# k22a.net
KiCad netlist of a schematic drawn in EAGLE
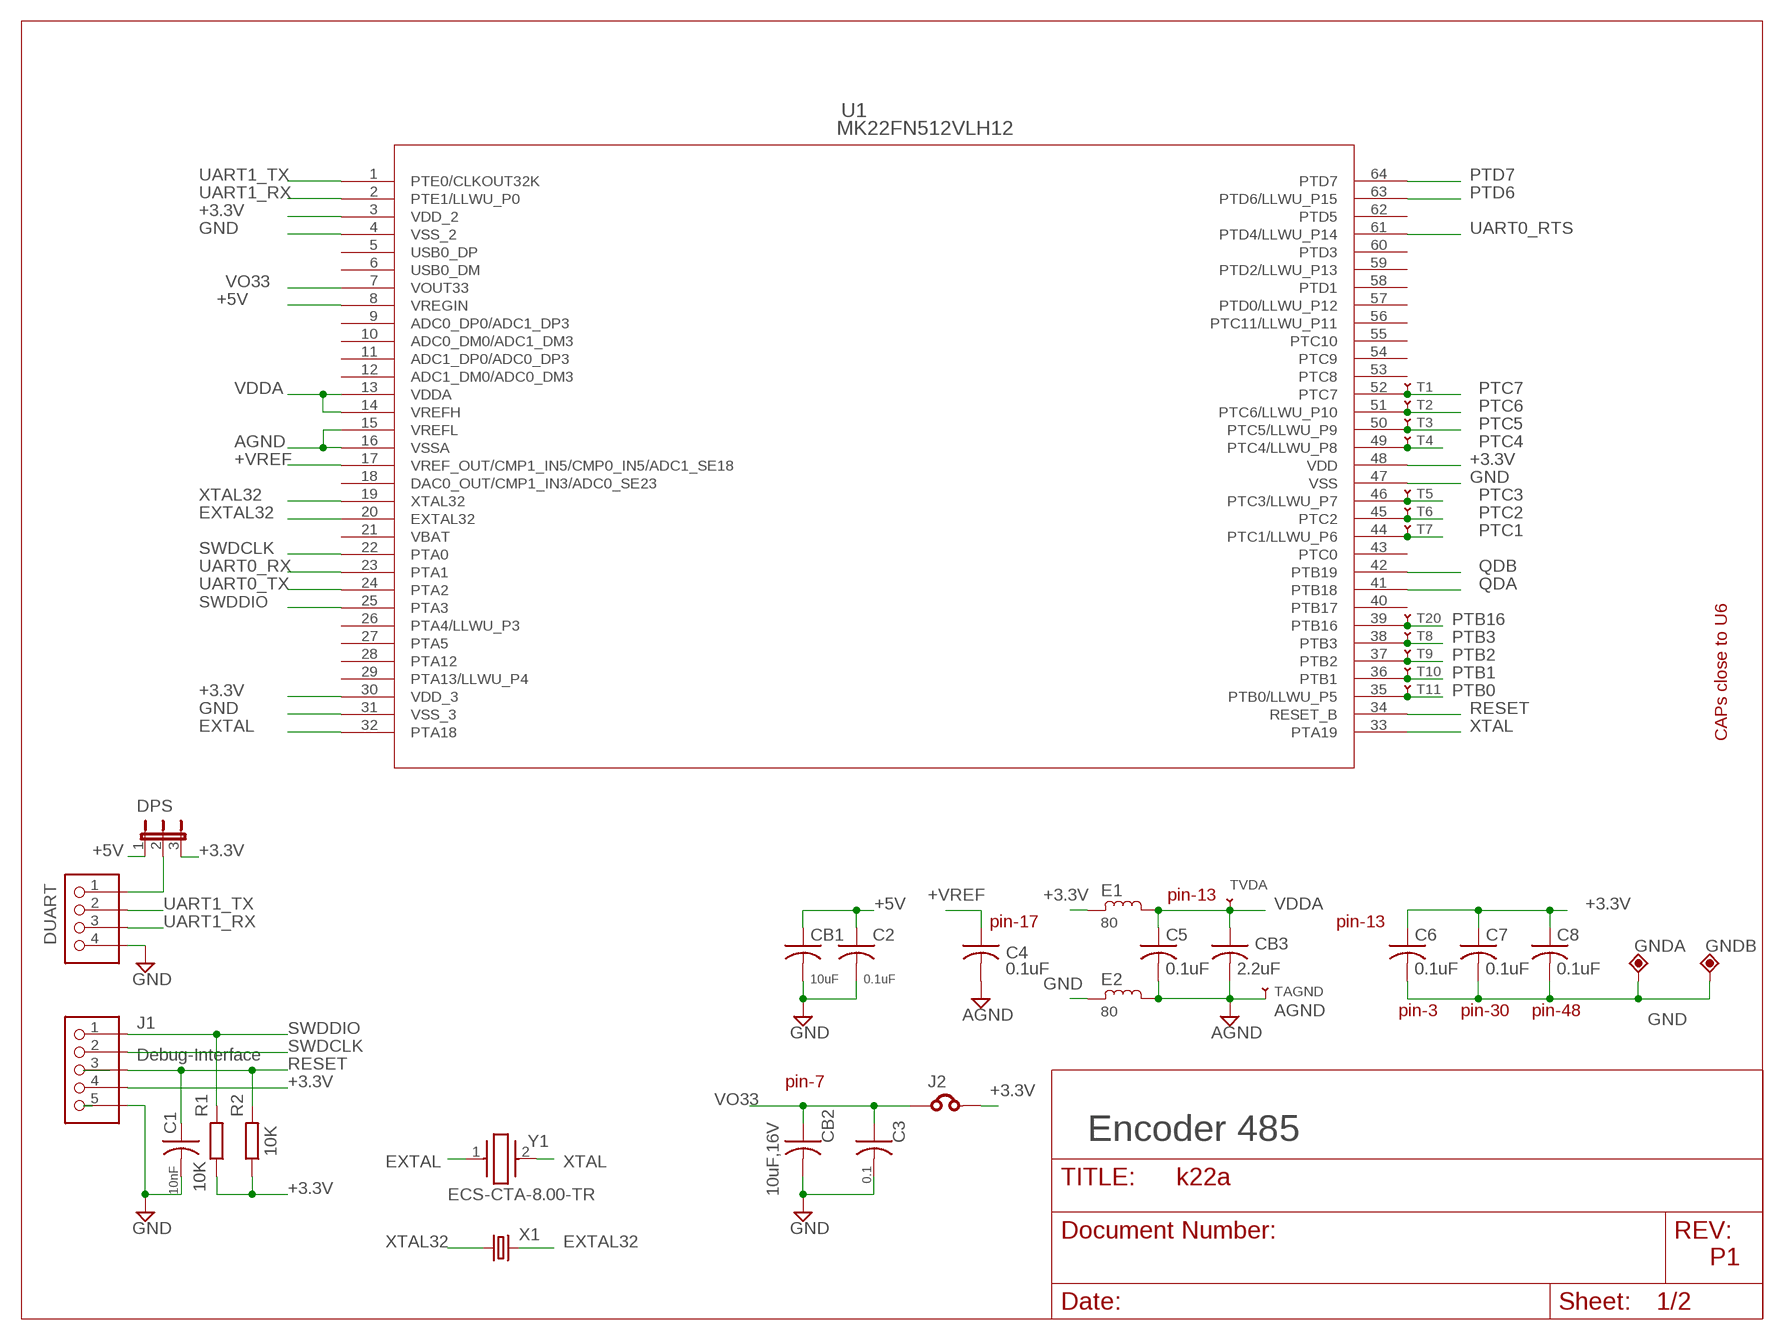
[diagram p0: schematic, sheet 1]
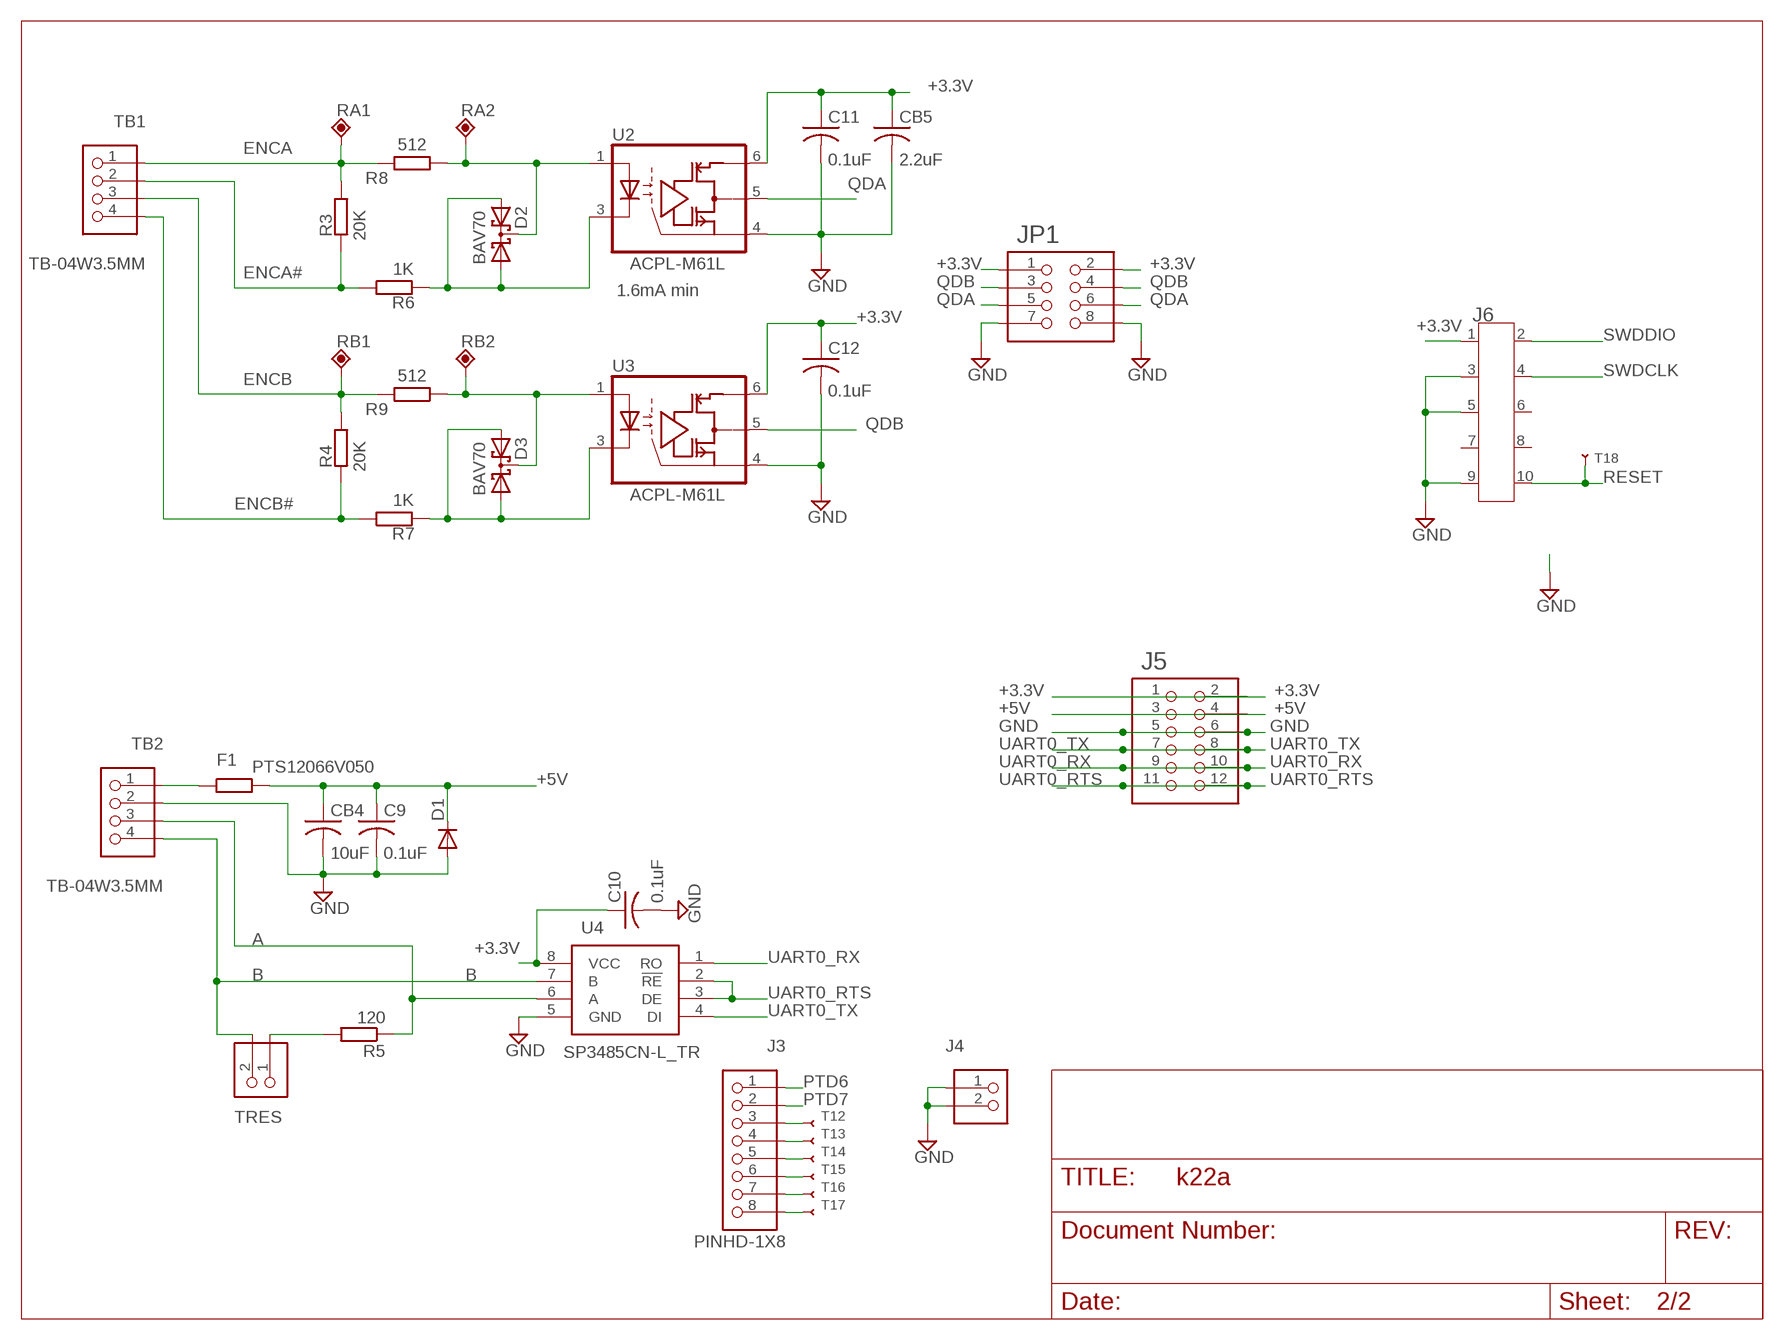
[diagram p1: schematic, sheet 2]

(export (version "E")
  (design (tool "Eeschema 10.0.6"))
  (components
    (comp (ref "C1")
      (value "10nF")
      (footprint "eagle-import:C1206")
      (libsource (lib "eagle-import") (part "C-USC1206"))
    )
    (comp (ref "C2")
      (value "0.1uF")
      (footprint "eagle-import:C1206")
      (libsource (lib "eagle-import") (part "C-USC1206"))
    )
    (comp (ref "C3")
      (value "0.1")
      (footprint "eagle-import:C1206")
      (libsource (lib "eagle-import") (part "C-USC1206"))
    )
    (comp (ref "C4")
      (value "0.1uF")
      (footprint "eagle-import:C1206")
      (libsource (lib "eagle-import") (part "C-USC1206"))
    )
    (comp (ref "C5")
      (value "0.1uF")
      (footprint "eagle-import:C1206")
      (libsource (lib "eagle-import") (part "C-USC1206"))
    )
    (comp (ref "C6")
      (value "0.1uF")
      (footprint "eagle-import:C1206")
      (libsource (lib "eagle-import") (part "C-USC1206"))
    )
    (comp (ref "C7")
      (value "0.1uF")
      (footprint "eagle-import:C1206")
      (libsource (lib "eagle-import") (part "C-USC1206"))
    )
    (comp (ref "C8")
      (value "0.1uF")
      (footprint "eagle-import:C1206")
      (libsource (lib "eagle-import") (part "C-USC1206"))
    )
    (comp (ref "CB1")
      (value "10uF")
      (footprint "eagle-import:C1206")
      (libsource (lib "eagle-import") (part "C-USC1206"))
    )
    (comp (ref "CB2")
      (value "10uF,16V")
      (footprint "eagle-import:C1206")
      (libsource (lib "eagle-import") (part "C-USC1206"))
    )
    (comp (ref "CB3")
      (value "2.2uF")
      (footprint "eagle-import:C1206")
      (libsource (lib "eagle-import") (part "C-USC1206"))
    )
    (comp (ref "DPS")
      (value "JP2E-0805")
      (footprint "eagle-import:R0805_2")
      (libsource (lib "eagle-import") (part "JP2E-0805"))
    )
    (comp (ref "DUART")
      (value "PINHD-1X4")
      (footprint "eagle-import:1X4")
      (libsource (lib "eagle-import") (part "PINHD-1X4"))
    )
    (comp (ref "E1")
      (value "80")
      (footprint "eagle-import:M1206")
      (libsource (lib "eagle-import") (part "ELDRC25SMD"))
    )
    (comp (ref "E2")
      (value "80")
      (footprint "eagle-import:M1206")
      (libsource (lib "eagle-import") (part "ELDRC25SMD"))
    )
    (comp (ref "GNDA")
      (value "TPP-PAD-032")
      (footprint "eagle-import:PAD-032")
      (libsource (lib "eagle-import") (part "TPP-PAD-032"))
    )
    (comp (ref "GNDB")
      (value "TPP-PAD-032")
      (footprint "eagle-import:PAD-032")
      (libsource (lib "eagle-import") (part "TPP-PAD-032"))
    )
    (comp (ref "J1")
      (value "PINHD-1X52MM")
      (footprint "eagle-import:1X5_2MM")
      (libsource (lib "eagle-import") (part "PINHD-1X52MM"))
    )
    (comp (ref "J2")
      (value "J0805")
      (footprint "eagle-import:R0805")
      (libsource (lib "eagle-import") (part "J0805"))
    )
    (comp (ref "R1")
      (value "10K")
      (footprint "eagle-import:M1206")
      (libsource (lib "eagle-import") (part "R-EU_M1206"))
    )
    (comp (ref "R2")
      (value "10K")
      (footprint "eagle-import:M1206")
      (libsource (lib "eagle-import") (part "R-EU_M1206"))
    )
    (comp (ref "T1")
      (value "ATP-40")
      (footprint "eagle-import:ATP-40")
      (libsource (lib "eagle-import") (part "ATP-40"))
    )
    (comp (ref "T2")
      (value "ATP-40")
      (footprint "eagle-import:ATP-40")
      (libsource (lib "eagle-import") (part "ATP-40"))
    )
    (comp (ref "T3")
      (value "ATP-40")
      (footprint "eagle-import:ATP-40")
      (libsource (lib "eagle-import") (part "ATP-40"))
    )
    (comp (ref "T4")
      (value "ATP-40")
      (footprint "eagle-import:ATP-40")
      (libsource (lib "eagle-import") (part "ATP-40"))
    )
    (comp (ref "T5")
      (value "ATP-40")
      (footprint "eagle-import:ATP-40")
      (libsource (lib "eagle-import") (part "ATP-40"))
    )
    (comp (ref "T6")
      (value "ATP-40")
      (footprint "eagle-import:ATP-40")
      (libsource (lib "eagle-import") (part "ATP-40"))
    )
    (comp (ref "T7")
      (value "ATP-40")
      (footprint "eagle-import:ATP-40")
      (libsource (lib "eagle-import") (part "ATP-40"))
    )
    (comp (ref "T8")
      (value "ATP-40")
      (footprint "eagle-import:ATP-40")
      (libsource (lib "eagle-import") (part "ATP-40"))
    )
    (comp (ref "T9")
      (value "ATP-40")
      (footprint "eagle-import:ATP-40")
      (libsource (lib "eagle-import") (part "ATP-40"))
    )
    (comp (ref "T10")
      (value "ATP-40")
      (footprint "eagle-import:ATP-40")
      (libsource (lib "eagle-import") (part "ATP-40"))
    )
    (comp (ref "T11")
      (value "ATP-40")
      (footprint "eagle-import:ATP-40")
      (libsource (lib "eagle-import") (part "ATP-40"))
    )
    (comp (ref "T20")
      (value "ATP-40")
      (footprint "eagle-import:ATP-40")
      (libsource (lib "eagle-import") (part "ATP-40"))
    )
    (comp (ref "TAGND")
      (value "ATP-40")
      (footprint "eagle-import:ATP-40")
      (libsource (lib "eagle-import") (part "ATP-40"))
    )
    (comp (ref "TVDA")
      (value "ATP-40")
      (footprint "eagle-import:ATP-40")
      (libsource (lib "eagle-import") (part "ATP-40"))
    )
    (comp (ref "U1")
      (value "MK22FN512VLH12")
      (footprint "eagle-import:LQFP-64_10X10X1.6")
      (fields (field (name "MANUFACTURER_PART_NUMBER") "mk22fn512vlh12"))
      (libsource (lib "eagle-import") (part "MK22FN512VLH12"))
    )
    (comp (ref "X1")
      (value "CRYSTALTC26V")
      (footprint "eagle-import:TC26V@1")
      (libsource (lib "eagle-import") (part "CRYSTALTC26V"))
    )
    (comp (ref "Y1")
      (value "ECS-CTA-8.00-TR")
      (footprint "eagle-import:ECSCTA800TR")
      (libsource (lib "eagle-import") (part "ECS-CTA-8.00-TR"))
    )
    (comp (ref "C9")
      (value "0.1uF")
      (footprint "eagle-import:C1206")
      (libsource (lib "eagle-import") (part "C-USC1206"))
    )
    (comp (ref "C10")
      (value "0.1uF")
      (footprint "eagle-import:C1206")
      (libsource (lib "eagle-import") (part "C-USC1206"))
    )
    (comp (ref "C11")
      (value "0.1uF")
      (footprint "eagle-import:C1206")
      (libsource (lib "eagle-import") (part "C-USC1206"))
    )
    (comp (ref "C12")
      (value "0.1uF")
      (footprint "eagle-import:C1206")
      (libsource (lib "eagle-import") (part "C-USC1206"))
    )
    (comp (ref "CB4")
      (value "10uF")
      (footprint "eagle-import:C1206")
      (libsource (lib "eagle-import") (part "C-USC1206"))
    )
    (comp (ref "CB5")
      (value "2.2uF")
      (footprint "eagle-import:C1206")
      (libsource (lib "eagle-import") (part "C-USC1206"))
    )
    (comp (ref "D1")
      (value "DIODE-DO214AC")
      (footprint "eagle-import:DO214AC")
      (libsource (lib "eagle-import") (part "DIODE-DO214AC"))
    )
    (comp (ref "D2")
      (value "BAV70")
      (footprint "eagle-import:SOT23")
      (fields (field (name "PARTNO") "BAV70-7-F"))
      (libsource (lib "eagle-import") (part "BAS70-05"))
    )
    (comp (ref "D3")
      (value "BAV70")
      (footprint "eagle-import:SOT23")
      (fields (field (name "PARTNO") "BAV70-7-F"))
      (libsource (lib "eagle-import") (part "BAS70-05"))
    )
    (comp (ref "F1")
      (value "PTS12066V050")
      (footprint "eagle-import:R1206")
      (libsource (lib "eagle-import") (part "R-EU_R1206"))
    )
    (comp (ref "J3")
      (value "PINHD-1X8")
      (footprint "eagle-import:1X8")
      (libsource (lib "eagle-import") (part "PINHD-1X8"))
    )
    (comp (ref "J4")
      (value "PINHD-1X2")
      (footprint "eagle-import:1X2")
      (libsource (lib "eagle-import") (part "PINHD-1X2"))
    )
    (comp (ref "J5")
      (value "PINHD-2X6")
      (footprint "eagle-import:2X6")
      (libsource (lib "eagle-import") (part "PINHD-2X6"))
    )
    (comp (ref "J6")
      (value "FTSH-105-01-L-DVMH")
      (footprint "eagle-import:CON10_2X5_FTSH_1")
      (libsource (lib "eagle-import") (part "FTSH-105-01-L-DVMH"))
    )
    (comp (ref "JP1")
      (value "PINHD-2X4")
      (footprint "eagle-import:2X4")
      (libsource (lib "eagle-import") (part "PINHD-2X4"))
    )
    (comp (ref "R3")
      (value "20K")
      (footprint "eagle-import:M1206")
      (libsource (lib "eagle-import") (part "R-EU_M1206"))
    )
    (comp (ref "R4")
      (value "20K")
      (footprint "eagle-import:M1206")
      (libsource (lib "eagle-import") (part "R-EU_M1206"))
    )
    (comp (ref "R5")
      (value "120")
      (footprint "eagle-import:M0805")
      (fields (field (name "PARTNO") "RC0805FR-072K7L"))
      (libsource (lib "eagle-import") (part "R-EU_M0805"))
    )
    (comp (ref "R6")
      (value "1K")
      (footprint "eagle-import:M1206")
      (libsource (lib "eagle-import") (part "R-EU_M1206"))
    )
    (comp (ref "R7")
      (value "1K")
      (footprint "eagle-import:M1206")
      (libsource (lib "eagle-import") (part "R-EU_M1206"))
    )
    (comp (ref "R8")
      (value "512")
      (footprint "eagle-import:M1206")
      (libsource (lib "eagle-import") (part "R-EU_M1206"))
    )
    (comp (ref "R9")
      (value "512")
      (footprint "eagle-import:M1206")
      (libsource (lib "eagle-import") (part "R-EU_M1206"))
    )
    (comp (ref "RA1")
      (value "TPP-PAD-032")
      (footprint "eagle-import:PAD-032")
      (libsource (lib "eagle-import") (part "TPP-PAD-032"))
    )
    (comp (ref "RA2")
      (value "TPP-PAD-032")
      (footprint "eagle-import:PAD-032")
      (libsource (lib "eagle-import") (part "TPP-PAD-032"))
    )
    (comp (ref "RB1")
      (value "TPP-PAD-032")
      (footprint "eagle-import:PAD-032")
      (libsource (lib "eagle-import") (part "TPP-PAD-032"))
    )
    (comp (ref "RB2")
      (value "TPP-PAD-032")
      (footprint "eagle-import:PAD-032")
      (libsource (lib "eagle-import") (part "TPP-PAD-032"))
    )
    (comp (ref "T12")
      (value "ATP-40")
      (footprint "eagle-import:ATP-40")
      (libsource (lib "eagle-import") (part "ATP-40"))
    )
    (comp (ref "T13")
      (value "ATP-40")
      (footprint "eagle-import:ATP-40")
      (libsource (lib "eagle-import") (part "ATP-40"))
    )
    (comp (ref "T14")
      (value "ATP-40")
      (footprint "eagle-import:ATP-40")
      (libsource (lib "eagle-import") (part "ATP-40"))
    )
    (comp (ref "T15")
      (value "ATP-40")
      (footprint "eagle-import:ATP-40")
      (libsource (lib "eagle-import") (part "ATP-40"))
    )
    (comp (ref "T16")
      (value "ATP-40")
      (footprint "eagle-import:ATP-40")
      (libsource (lib "eagle-import") (part "ATP-40"))
    )
    (comp (ref "T17")
      (value "ATP-40")
      (footprint "eagle-import:ATP-40")
      (libsource (lib "eagle-import") (part "ATP-40"))
    )
    (comp (ref "T18")
      (value "ATP-40")
      (footprint "eagle-import:ATP-40")
      (libsource (lib "eagle-import") (part "ATP-40"))
    )
    (comp (ref "TB1")
      (value "TB-04W3.5MM")
      (footprint "eagle-import:WURTH35-04")
      (libsource (lib "eagle-import") (part "TB-04W3.5MM"))
    )
    (comp (ref "TB2")
      (value "TB-04W3.5MM")
      (footprint "eagle-import:WURTH35-04")
      (libsource (lib "eagle-import") (part "TB-04W3.5MM"))
    )
    (comp (ref "TRES")
      (value "PINHD-1X2")
      (footprint "eagle-import:1X2")
      (libsource (lib "eagle-import") (part "PINHD-1X2"))
    )
    (comp (ref "U2")
      (value "ACPL-M61L")
      (footprint "eagle-import:SO-5")
      (fields (field (name "PARTNO") "ACPL-M61L-000E"))
      (libsource (lib "eagle-import") (part "ACPL-M61LSO5"))
    )
    (comp (ref "U3")
      (value "ACPL-M61L")
      (footprint "eagle-import:SO-5")
      (fields (field (name "PARTNO") "ACPL-M61L-000E"))
      (libsource (lib "eagle-import") (part "ACPL-M61LSO5"))
    )
    (comp (ref "U4")
      (value "SP3485CN-L_TR")
      (footprint "eagle-import:SOIC127P600X175-8N")
      (fields
        (field (name "ARROW_PART_NUMBER") "SP3485CN-L/TR")
        (field (name "MOUSER_PART_NUMBER") "701-SP3485CN-L/TR")
      )
      (libsource (lib "eagle-import") (part "SP3485CN-L_TR"))
    )
  )
  (nets
    (net (code "1") (name "+3.3V") (class "Default")
      (node (ref "C10") (pin "1") (pinfunction "1_1") (pintype "passive"))
      (node (ref "C11") (pin "1") (pinfunction "1_1") (pintype "passive"))
      (node (ref "C12") (pin "1") (pinfunction "1_1") (pintype "passive"))
      (node (ref "C6") (pin "1") (pinfunction "1_1") (pintype "passive"))
      (node (ref "C7") (pin "1") (pinfunction "1_1") (pintype "passive"))
      (node (ref "C8") (pin "1") (pinfunction "1_1") (pintype "passive"))
      (node (ref "CB5") (pin "1") (pinfunction "1_1") (pintype "passive"))
      (node (ref "DPS") (pin "3") (pinfunction "3_3") (pintype "passive"))
      (node (ref "E1") (pin "1") (pinfunction "1_1") (pintype "passive"))
      (node (ref "J1") (pin "4") (pinfunction "4_4") (pintype "passive"))
      (node (ref "J2") (pin "2") (pinfunction "2_2") (pintype "passive"))
      (node (ref "J5") (pin "1") (pinfunction "1_1") (pintype "passive"))
      (node (ref "J5") (pin "2") (pinfunction "2_2") (pintype "passive"))
      (node (ref "J6") (pin "1") (pinfunction "1_1") (pintype "passive"))
      (node (ref "JP1") (pin "1") (pinfunction "1_1") (pintype "passive"))
      (node (ref "JP1") (pin "2") (pinfunction "2_2") (pintype "passive"))
      (node (ref "R1") (pin "1") (pinfunction "1_1") (pintype "passive"))
      (node (ref "R2") (pin "1") (pinfunction "1_1") (pintype "passive"))
      (node (ref "U1") (pin "3") (pinfunction "VDD_2_3") (pintype "power_in"))
      (node (ref "U1") (pin "30") (pinfunction "VDD_3_30") (pintype "power_in"))
      (node (ref "U1") (pin "48") (pinfunction "VDD_48") (pintype "power_in"))
      (node (ref "U2") (pin "6") (pinfunction "VCC_6") (pintype "passive"))
      (node (ref "U3") (pin "6") (pinfunction "VCC_6") (pintype "passive"))
      (node (ref "U4") (pin "8") (pinfunction "VCC_8") (pintype "bidirectional"))
    )
    (net (code "2") (name "+5V") (class "Default")
      (node (ref "C2") (pin "1") (pinfunction "1_1") (pintype "passive"))
      (node (ref "C9") (pin "1") (pinfunction "1_1") (pintype "passive"))
      (node (ref "CB1") (pin "1") (pinfunction "1_1") (pintype "passive"))
      (node (ref "CB4") (pin "1") (pinfunction "1_1") (pintype "passive"))
      (node (ref "D1") (pin "C") (pinfunction "C_C") (pintype "passive"))
      (node (ref "DPS") (pin "1") (pinfunction "1_1") (pintype "passive"))
      (node (ref "F1") (pin "2") (pinfunction "2_2") (pintype "passive"))
      (node (ref "J5") (pin "3") (pinfunction "3_3") (pintype "passive"))
      (node (ref "J5") (pin "4") (pinfunction "4_4") (pintype "passive"))
      (node (ref "U1") (pin "8") (pinfunction "VREGIN_8") (pintype "input"))
    )
    (net (code "3") (name "+VREF") (class "Default")
      (node (ref "C4") (pin "1") (pinfunction "1_1") (pintype "passive"))
      (node (ref "U1") (pin "17") (pinfunction "VREF_OUT/CMP1_IN5/CMP0_IN5/ADC1_SE18_17") (pintype "bidirectional"))
    )
    (net (code "4") (name "A") (class "Default")
      (node (ref "R5") (pin "1") (pinfunction "1_1") (pintype "passive"))
      (node (ref "TB2") (pin "3") (pinfunction "3_3") (pintype "passive"))
      (node (ref "U4") (pin "6") (pinfunction "A_6") (pintype "bidirectional"))
    )
    (net (code "5") (name "AGND") (class "Default")
      (node (ref "C4") (pin "2") (pinfunction "2_2") (pintype "passive"))
      (node (ref "C5") (pin "2") (pinfunction "2_2") (pintype "passive"))
      (node (ref "CB3") (pin "2") (pinfunction "2_2") (pintype "passive"))
      (node (ref "E2") (pin "2") (pinfunction "2_2") (pintype "passive"))
      (node (ref "TAGND") (pin "P") (pinfunction "TP_P") (pintype "passive"))
      (node (ref "U1") (pin "15") (pinfunction "VREFL_15") (pintype "power_in"))
      (node (ref "U1") (pin "16") (pinfunction "VSSA_16") (pintype "power_in"))
    )
    (net (code "6") (name "B") (class "Default")
      (node (ref "TB2") (pin "4") (pinfunction "4_4") (pintype "passive"))
      (node (ref "TRES") (pin "2") (pinfunction "2_2") (pintype "passive"))
      (node (ref "U4") (pin "7") (pinfunction "B_7") (pintype "bidirectional"))
    )
    (net (code "7") (name "ENCA") (class "Default")
      (node (ref "R3") (pin "1") (pinfunction "1_1") (pintype "passive"))
      (node (ref "R8") (pin "2") (pinfunction "2_2") (pintype "passive"))
      (node (ref "RA1") (pin "1") (pinfunction "TP_1") (pintype "passive"))
      (node (ref "TB1") (pin "1") (pinfunction "1_1") (pintype "passive"))
    )
    (net (code "8") (name "ENCA#") (class "Default")
      (node (ref "R3") (pin "2") (pinfunction "2_2") (pintype "passive"))
      (node (ref "R6") (pin "1") (pinfunction "1_1") (pintype "passive"))
      (node (ref "TB1") (pin "2") (pinfunction "2_2") (pintype "passive"))
    )
    (net (code "9") (name "ENCB") (class "Default")
      (node (ref "R4") (pin "1") (pinfunction "1_1") (pintype "passive"))
      (node (ref "R9") (pin "2") (pinfunction "2_2") (pintype "passive"))
      (node (ref "RB1") (pin "1") (pinfunction "TP_1") (pintype "passive"))
      (node (ref "TB1") (pin "3") (pinfunction "3_3") (pintype "passive"))
    )
    (net (code "10") (name "ENCB#") (class "Default")
      (node (ref "R4") (pin "2") (pinfunction "2_2") (pintype "passive"))
      (node (ref "R7") (pin "1") (pinfunction "1_1") (pintype "passive"))
      (node (ref "TB1") (pin "4") (pinfunction "4_4") (pintype "passive"))
    )
    (net (code "11") (name "EXTAL") (class "Default")
      (node (ref "U1") (pin "32") (pinfunction "PTA18_32") (pintype "bidirectional"))
      (node (ref "Y1") (pin "1") (pinfunction "1_1") (pintype "bidirectional"))
    )
    (net (code "12") (name "EXTAL32") (class "Default")
      (node (ref "U1") (pin "20") (pinfunction "EXTAL32_20") (pintype "passive"))
      (node (ref "X1") (pin "2") (pinfunction "2_2") (pintype "passive"))
    )
    (net (code "13") (name "GND") (class "Default")
      (node (ref "C1") (pin "2") (pinfunction "2_2") (pintype "passive"))
      (node (ref "C10") (pin "2") (pinfunction "2_2") (pintype "passive"))
      (node (ref "C11") (pin "2") (pinfunction "2_2") (pintype "passive"))
      (node (ref "C12") (pin "2") (pinfunction "2_2") (pintype "passive"))
      (node (ref "C2") (pin "2") (pinfunction "2_2") (pintype "passive"))
      (node (ref "C3") (pin "2") (pinfunction "2_2") (pintype "passive"))
      (node (ref "C6") (pin "2") (pinfunction "2_2") (pintype "passive"))
      (node (ref "C7") (pin "2") (pinfunction "2_2") (pintype "passive"))
      (node (ref "C8") (pin "2") (pinfunction "2_2") (pintype "passive"))
      (node (ref "C9") (pin "2") (pinfunction "2_2") (pintype "passive"))
      (node (ref "CB1") (pin "2") (pinfunction "2_2") (pintype "passive"))
      (node (ref "CB2") (pin "2") (pinfunction "2_2") (pintype "passive"))
      (node (ref "CB4") (pin "2") (pinfunction "2_2") (pintype "passive"))
      (node (ref "CB5") (pin "2") (pinfunction "2_2") (pintype "passive"))
      (node (ref "D1") (pin "A") (pinfunction "A_A") (pintype "passive"))
      (node (ref "DUART") (pin "4") (pinfunction "4_4") (pintype "passive"))
      (node (ref "E2") (pin "1") (pinfunction "1_1") (pintype "passive"))
      (node (ref "GNDA") (pin "1") (pinfunction "TP_1") (pintype "passive"))
      (node (ref "GNDB") (pin "1") (pinfunction "TP_1") (pintype "passive"))
      (node (ref "J1") (pin "5") (pinfunction "5_5") (pintype "passive"))
      (node (ref "J4") (pin "1") (pinfunction "1_1") (pintype "passive"))
      (node (ref "J4") (pin "2") (pinfunction "2_2") (pintype "passive"))
      (node (ref "J5") (pin "5") (pinfunction "5_5") (pintype "passive"))
      (node (ref "J5") (pin "6") (pinfunction "6_6") (pintype "passive"))
      (node (ref "J6") (pin "3") (pinfunction "3_3") (pintype "passive"))
      (node (ref "J6") (pin "5") (pinfunction "5_5") (pintype "passive"))
      (node (ref "J6") (pin "9") (pinfunction "9_9") (pintype "passive"))
      (node (ref "JP1") (pin "7") (pinfunction "7_7") (pintype "passive"))
      (node (ref "JP1") (pin "8") (pinfunction "8_8") (pintype "passive"))
      (node (ref "TB2") (pin "2") (pinfunction "2_2") (pintype "passive"))
      (node (ref "U1") (pin "31") (pinfunction "VSS_3_31") (pintype "power_in"))
      (node (ref "U1") (pin "4") (pinfunction "VSS_2_4") (pintype "power_in"))
      (node (ref "U1") (pin "47") (pinfunction "VSS_47") (pintype "power_in"))
      (node (ref "U2") (pin "4") (pinfunction "GND_4") (pintype "passive"))
      (node (ref "U3") (pin "4") (pinfunction "GND_4") (pintype "passive"))
      (node (ref "U4") (pin "5") (pinfunction "GND_5") (pintype "bidirectional"))
    )
    (net (code "14") (name "Net-(D2-A1)") (class "Default")
      (node (ref "D2") (pin "1") (pinfunction "A1_1") (pintype "passive"))
      (node (ref "D2") (pin "2") (pinfunction "A2_2") (pintype "passive"))
      (node (ref "R6") (pin "2") (pinfunction "2_2") (pintype "passive"))
      (node (ref "U2") (pin "3") (pinfunction "C_3") (pintype "passive"))
    )
    (net (code "15") (name "Net-(D2-C)") (class "Default")
      (node (ref "D2") (pin "3") (pinfunction "C_3") (pintype "passive"))
      (node (ref "R8") (pin "1") (pinfunction "1_1") (pintype "passive"))
      (node (ref "RA2") (pin "1") (pinfunction "TP_1") (pintype "passive"))
      (node (ref "U2") (pin "1") (pinfunction "A_1") (pintype "passive"))
    )
    (net (code "16") (name "Net-(D3-A1)") (class "Default")
      (node (ref "D3") (pin "1") (pinfunction "A1_1") (pintype "passive"))
      (node (ref "D3") (pin "2") (pinfunction "A2_2") (pintype "passive"))
      (node (ref "R7") (pin "2") (pinfunction "2_2") (pintype "passive"))
      (node (ref "U3") (pin "3") (pinfunction "C_3") (pintype "passive"))
    )
    (net (code "17") (name "Net-(D3-C)") (class "Default")
      (node (ref "D3") (pin "3") (pinfunction "C_3") (pintype "passive"))
      (node (ref "R9") (pin "1") (pinfunction "1_1") (pintype "passive"))
      (node (ref "RB2") (pin "1") (pinfunction "TP_1") (pintype "passive"))
      (node (ref "U3") (pin "1") (pinfunction "A_1") (pintype "passive"))
    )
    (net (code "18") (name "Net-(DPS-Pad2)") (class "Default")
      (node (ref "DPS") (pin "2") (pinfunction "2_2") (pintype "passive"))
      (node (ref "DUART") (pin "1") (pinfunction "1_1") (pintype "passive"))
    )
    (net (code "19") (name "Net-(F1-Pad1)") (class "Default")
      (node (ref "F1") (pin "1") (pinfunction "1_1") (pintype "passive"))
      (node (ref "TB2") (pin "1") (pinfunction "1_1") (pintype "passive"))
    )
    (net (code "20") (name "Net-(R5-Pad2)") (class "Default")
      (node (ref "R5") (pin "2") (pinfunction "2_2") (pintype "passive"))
      (node (ref "TRES") (pin "1") (pinfunction "1_1") (pintype "passive"))
    )
    (net (code "21") (name "Net-(T12-TP)") (class "Default")
      (node (ref "J3") (pin "3") (pinfunction "3_3") (pintype "passive"))
      (node (ref "T12") (pin "P") (pinfunction "TP_P") (pintype "passive"))
    )
    (net (code "22") (name "Net-(T13-TP)") (class "Default")
      (node (ref "J3") (pin "4") (pinfunction "4_4") (pintype "passive"))
      (node (ref "T13") (pin "P") (pinfunction "TP_P") (pintype "passive"))
    )
    (net (code "23") (name "Net-(T14-TP)") (class "Default")
      (node (ref "J3") (pin "5") (pinfunction "5_5") (pintype "passive"))
      (node (ref "T14") (pin "P") (pinfunction "TP_P") (pintype "passive"))
    )
    (net (code "24") (name "Net-(T15-TP)") (class "Default")
      (node (ref "J3") (pin "6") (pinfunction "6_6") (pintype "passive"))
      (node (ref "T15") (pin "P") (pinfunction "TP_P") (pintype "passive"))
    )
    (net (code "25") (name "Net-(T16-TP)") (class "Default")
      (node (ref "J3") (pin "7") (pinfunction "7_7") (pintype "passive"))
      (node (ref "T16") (pin "P") (pinfunction "TP_P") (pintype "passive"))
    )
    (net (code "26") (name "Net-(T17-TP)") (class "Default")
      (node (ref "J3") (pin "8") (pinfunction "8_8") (pintype "passive"))
      (node (ref "T17") (pin "P") (pinfunction "TP_P") (pintype "passive"))
    )
    (net (code "27") (name "PTB0") (class "Default")
      (node (ref "T11") (pin "P") (pinfunction "TP_P") (pintype "passive"))
      (node (ref "U1") (pin "35") (pinfunction "PTB0/LLWU_P5_35") (pintype "bidirectional"))
    )
    (net (code "28") (name "PTB1") (class "Default")
      (node (ref "T10") (pin "P") (pinfunction "TP_P") (pintype "passive"))
      (node (ref "U1") (pin "36") (pinfunction "PTB1_36") (pintype "bidirectional"))
    )
    (net (code "29") (name "PTB2") (class "Default")
      (node (ref "T9") (pin "P") (pinfunction "TP_P") (pintype "passive"))
      (node (ref "U1") (pin "37") (pinfunction "PTB2_37") (pintype "bidirectional"))
    )
    (net (code "30") (name "PTB3") (class "Default")
      (node (ref "T8") (pin "P") (pinfunction "TP_P") (pintype "passive"))
      (node (ref "U1") (pin "38") (pinfunction "PTB3_38") (pintype "bidirectional"))
    )
    (net (code "31") (name "PTB16") (class "Default")
      (node (ref "T20") (pin "P") (pinfunction "TP_P") (pintype "passive"))
      (node (ref "U1") (pin "39") (pinfunction "PTB16_39") (pintype "bidirectional"))
    )
    (net (code "32") (name "PTC1") (class "Default")
      (node (ref "T7") (pin "P") (pinfunction "TP_P") (pintype "passive"))
      (node (ref "U1") (pin "44") (pinfunction "PTC1/LLWU_P6_44") (pintype "bidirectional"))
    )
    (net (code "33") (name "PTC2") (class "Default")
      (node (ref "T6") (pin "P") (pinfunction "TP_P") (pintype "passive"))
      (node (ref "U1") (pin "45") (pinfunction "PTC2_45") (pintype "bidirectional"))
    )
    (net (code "34") (name "PTC3") (class "Default")
      (node (ref "T5") (pin "P") (pinfunction "TP_P") (pintype "passive"))
      (node (ref "U1") (pin "46") (pinfunction "PTC3/LLWU_P7_46") (pintype "bidirectional"))
    )
    (net (code "35") (name "PTC4") (class "Default")
      (node (ref "T4") (pin "P") (pinfunction "TP_P") (pintype "passive"))
      (node (ref "U1") (pin "49") (pinfunction "PTC4/LLWU_P8_49") (pintype "bidirectional"))
    )
    (net (code "36") (name "PTC5") (class "Default")
      (node (ref "T3") (pin "P") (pinfunction "TP_P") (pintype "passive"))
      (node (ref "U1") (pin "50") (pinfunction "PTC5/LLWU_P9_50") (pintype "bidirectional"))
    )
    (net (code "37") (name "PTC6") (class "Default")
      (node (ref "T2") (pin "P") (pinfunction "TP_P") (pintype "passive"))
      (node (ref "U1") (pin "51") (pinfunction "PTC6/LLWU_P10_51") (pintype "bidirectional"))
    )
    (net (code "38") (name "PTC7") (class "Default")
      (node (ref "T1") (pin "P") (pinfunction "TP_P") (pintype "passive"))
      (node (ref "U1") (pin "52") (pinfunction "PTC7_52") (pintype "bidirectional"))
    )
    (net (code "39") (name "PTD6") (class "Default")
      (node (ref "J3") (pin "1") (pinfunction "1_1") (pintype "passive"))
      (node (ref "U1") (pin "63") (pinfunction "PTD6/LLWU_P15_63") (pintype "bidirectional"))
    )
    (net (code "40") (name "PTD7") (class "Default")
      (node (ref "J3") (pin "2") (pinfunction "2_2") (pintype "passive"))
      (node (ref "U1") (pin "64") (pinfunction "PTD7_64") (pintype "bidirectional"))
    )
    (net (code "41") (name "QDA") (class "Default")
      (node (ref "JP1") (pin "5") (pinfunction "5_5") (pintype "passive"))
      (node (ref "JP1") (pin "6") (pinfunction "6_6") (pintype "passive"))
      (node (ref "U1") (pin "41") (pinfunction "PTB18_41") (pintype "bidirectional"))
      (node (ref "U2") (pin "5") (pinfunction "OUT_5") (pintype "passive"))
    )
    (net (code "42") (name "QDB") (class "Default")
      (node (ref "JP1") (pin "3") (pinfunction "3_3") (pintype "passive"))
      (node (ref "JP1") (pin "4") (pinfunction "4_4") (pintype "passive"))
      (node (ref "U1") (pin "42") (pinfunction "PTB19_42") (pintype "bidirectional"))
      (node (ref "U3") (pin "5") (pinfunction "OUT_5") (pintype "passive"))
    )
    (net (code "43") (name "RESET") (class "Default")
      (node (ref "C1") (pin "1") (pinfunction "1_1") (pintype "passive"))
      (node (ref "J1") (pin "3") (pinfunction "3_3") (pintype "passive"))
      (node (ref "J6") (pin "10") (pinfunction "10_10") (pintype "passive"))
      (node (ref "R2") (pin "2") (pinfunction "2_2") (pintype "passive"))
      (node (ref "T18") (pin "P") (pinfunction "TP_P") (pintype "passive"))
      (node (ref "U1") (pin "34") (pinfunction "RESET_B_34") (pintype "passive"))
    )
    (net (code "44") (name "SWDCLK") (class "Default")
      (node (ref "J1") (pin "2") (pinfunction "2_2") (pintype "passive"))
      (node (ref "J6") (pin "4") (pinfunction "4_4") (pintype "passive"))
      (node (ref "U1") (pin "22") (pinfunction "PTA0_22") (pintype "bidirectional"))
    )
    (net (code "45") (name "SWDDIO") (class "Default")
      (node (ref "J1") (pin "1") (pinfunction "1_1") (pintype "passive"))
      (node (ref "J6") (pin "2") (pinfunction "2_2") (pintype "passive"))
      (node (ref "R1") (pin "2") (pinfunction "2_2") (pintype "passive"))
      (node (ref "U1") (pin "25") (pinfunction "PTA3_25") (pintype "bidirectional"))
    )
    (net (code "46") (name "UART0_RTS") (class "Default")
      (node (ref "J5") (pin "11") (pinfunction "11_11") (pintype "passive"))
      (node (ref "J5") (pin "12") (pinfunction "12_12") (pintype "passive"))
      (node (ref "U1") (pin "61") (pinfunction "PTD4/LLWU_P14_61") (pintype "bidirectional"))
      (node (ref "U4") (pin "2") (pinfunction "~{RE}_2") (pintype "bidirectional"))
      (node (ref "U4") (pin "3") (pinfunction "DE_3") (pintype "bidirectional"))
    )
    (net (code "47") (name "UART0_RX") (class "Default")
      (node (ref "J5") (pin "10") (pinfunction "10_10") (pintype "passive"))
      (node (ref "J5") (pin "9") (pinfunction "9_9") (pintype "passive"))
      (node (ref "U1") (pin "23") (pinfunction "PTA1_23") (pintype "bidirectional"))
      (node (ref "U4") (pin "1") (pinfunction "RO_1") (pintype "bidirectional"))
    )
    (net (code "48") (name "UART0_TX") (class "Default")
      (node (ref "J5") (pin "7") (pinfunction "7_7") (pintype "passive"))
      (node (ref "J5") (pin "8") (pinfunction "8_8") (pintype "passive"))
      (node (ref "U1") (pin "24") (pinfunction "PTA2_24") (pintype "bidirectional"))
      (node (ref "U4") (pin "4") (pinfunction "DI_4") (pintype "bidirectional"))
    )
    (net (code "49") (name "UART1_RX") (class "Default")
      (node (ref "DUART") (pin "3") (pinfunction "3_3") (pintype "passive"))
      (node (ref "U1") (pin "2") (pinfunction "PTE1/LLWU_P0_2") (pintype "bidirectional"))
    )
    (net (code "50") (name "UART1_TX") (class "Default")
      (node (ref "DUART") (pin "2") (pinfunction "2_2") (pintype "passive"))
      (node (ref "U1") (pin "1") (pinfunction "PTE0/CLKOUT32K_1") (pintype "bidirectional"))
    )
    (net (code "51") (name "VBAT") (class "Default")
      (node (ref "U1") (pin "21") (pinfunction "VBAT_21") (pintype "power_in"))
    )
    (net (code "52") (name "VDDA") (class "Default")
      (node (ref "C5") (pin "1") (pinfunction "1_1") (pintype "passive"))
      (node (ref "CB3") (pin "1") (pinfunction "1_1") (pintype "passive"))
      (node (ref "E1") (pin "2") (pinfunction "2_2") (pintype "passive"))
      (node (ref "TVDA") (pin "P") (pinfunction "TP_P") (pintype "passive"))
      (node (ref "U1") (pin "13") (pinfunction "VDDA_13") (pintype "power_in"))
      (node (ref "U1") (pin "14") (pinfunction "VREFH_14") (pintype "power_in"))
    )
    (net (code "53") (name "VO33") (class "Default")
      (node (ref "C3") (pin "1") (pinfunction "1_1") (pintype "passive"))
      (node (ref "CB2") (pin "1") (pinfunction "1_1") (pintype "passive"))
      (node (ref "J2") (pin "1") (pinfunction "1_1") (pintype "passive"))
      (node (ref "U1") (pin "7") (pinfunction "VOUT33_7") (pintype "output"))
    )
    (net (code "54") (name "XTAL") (class "Default")
      (node (ref "U1") (pin "33") (pinfunction "PTA19_33") (pintype "bidirectional"))
      (node (ref "Y1") (pin "2") (pinfunction "2_2") (pintype "bidirectional"))
    )
    (net (code "55") (name "XTAL32") (class "Default")
      (node (ref "U1") (pin "19") (pinfunction "XTAL32_19") (pintype "passive"))
      (node (ref "X1") (pin "1") (pinfunction "1_1") (pintype "passive"))
    )
    (net (code "56") (name "unconnected-(J6-Pad6)") (class "Default")
      (node (ref "J6") (pin "6") (pinfunction "6_6") (pintype "passive"))
    )
    (net (code "57") (name "unconnected-(J6-Pad7)") (class "Default")
      (node (ref "J6") (pin "7") (pinfunction "7_7") (pintype "passive"))
    )
    (net (code "58") (name "unconnected-(J6-Pad8)") (class "Default")
      (node (ref "J6") (pin "8") (pinfunction "8_8") (pintype "passive"))
    )
    (net (code "59") (name "unconnected-(U1-ADC0_DM0{slash}ADC1_DM3-Pad10)") (class "Default")
      (node (ref "U1") (pin "10") (pinfunction "ADC0_DM0/ADC1_DM3_10") (pintype "bidirectional"))
    )
    (net (code "60") (name "unconnected-(U1-ADC0_DP0{slash}ADC1_DP3-Pad9)") (class "Default")
      (node (ref "U1") (pin "9") (pinfunction "ADC0_DP0/ADC1_DP3_9") (pintype "bidirectional"))
    )
    (net (code "61") (name "unconnected-(U1-ADC1_DM0{slash}ADC0_DM3-Pad12)") (class "Default")
      (node (ref "U1") (pin "12") (pinfunction "ADC1_DM0/ADC0_DM3_12") (pintype "bidirectional"))
    )
    (net (code "62") (name "unconnected-(U1-ADC1_DP0{slash}ADC0_DP3-Pad11)") (class "Default")
      (node (ref "U1") (pin "11") (pinfunction "ADC1_DP0/ADC0_DP3_11") (pintype "bidirectional"))
    )
    (net (code "63") (name "unconnected-(U1-DAC0_OUT{slash}CMP1_IN3{slash}ADC0_SE23-Pad18)") (class "Default")
      (node (ref "U1") (pin "18") (pinfunction "DAC0_OUT/CMP1_IN3/ADC0_SE23_18") (pintype "bidirectional"))
    )
    (net (code "64") (name "unconnected-(U1-PTA4{slash}LLWU_P3-Pad26)") (class "Default")
      (node (ref "U1") (pin "26") (pinfunction "PTA4/LLWU_P3_26") (pintype "bidirectional"))
    )
    (net (code "65") (name "unconnected-(U1-PTA5-Pad27)") (class "Default")
      (node (ref "U1") (pin "27") (pinfunction "PTA5_27") (pintype "bidirectional"))
    )
    (net (code "66") (name "unconnected-(U1-PTA12-Pad28)") (class "Default")
      (node (ref "U1") (pin "28") (pinfunction "PTA12_28") (pintype "bidirectional"))
    )
    (net (code "67") (name "unconnected-(U1-PTA13{slash}LLWU_P4-Pad29)") (class "Default")
      (node (ref "U1") (pin "29") (pinfunction "PTA13/LLWU_P4_29") (pintype "bidirectional"))
    )
    (net (code "68") (name "unconnected-(U1-PTB17-Pad40)") (class "Default")
      (node (ref "U1") (pin "40") (pinfunction "PTB17_40") (pintype "bidirectional"))
    )
    (net (code "69") (name "unconnected-(U1-PTC0-Pad43)") (class "Default")
      (node (ref "U1") (pin "43") (pinfunction "PTC0_43") (pintype "bidirectional"))
    )
    (net (code "70") (name "unconnected-(U1-PTC8-Pad53)") (class "Default")
      (node (ref "U1") (pin "53") (pinfunction "PTC8_53") (pintype "bidirectional"))
    )
    (net (code "71") (name "unconnected-(U1-PTC9-Pad54)") (class "Default")
      (node (ref "U1") (pin "54") (pinfunction "PTC9_54") (pintype "bidirectional"))
    )
    (net (code "72") (name "unconnected-(U1-PTC10-Pad55)") (class "Default")
      (node (ref "U1") (pin "55") (pinfunction "PTC10_55") (pintype "bidirectional"))
    )
    (net (code "73") (name "unconnected-(U1-PTC11{slash}LLWU_P11-Pad56)") (class "Default")
      (node (ref "U1") (pin "56") (pinfunction "PTC11/LLWU_P11_56") (pintype "bidirectional"))
    )
    (net (code "74") (name "unconnected-(U1-PTD0{slash}LLWU_P12-Pad57)") (class "Default")
      (node (ref "U1") (pin "57") (pinfunction "PTD0/LLWU_P12_57") (pintype "bidirectional"))
    )
    (net (code "75") (name "unconnected-(U1-PTD1-Pad58)") (class "Default")
      (node (ref "U1") (pin "58") (pinfunction "PTD1_58") (pintype "bidirectional"))
    )
    (net (code "76") (name "unconnected-(U1-PTD2{slash}LLWU_P13-Pad59)") (class "Default")
      (node (ref "U1") (pin "59") (pinfunction "PTD2/LLWU_P13_59") (pintype "bidirectional"))
    )
    (net (code "77") (name "unconnected-(U1-PTD3-Pad60)") (class "Default")
      (node (ref "U1") (pin "60") (pinfunction "PTD3_60") (pintype "bidirectional"))
    )
    (net (code "78") (name "unconnected-(U1-PTD5-Pad62)") (class "Default")
      (node (ref "U1") (pin "62") (pinfunction "PTD5_62") (pintype "bidirectional"))
    )
    (net (code "79") (name "unconnected-(U1-USB0_DM-Pad6)") (class "Default")
      (node (ref "U1") (pin "6") (pinfunction "USB0_DM_6") (pintype "passive"))
    )
    (net (code "80") (name "unconnected-(U1-USB0_DP-Pad5)") (class "Default")
      (node (ref "U1") (pin "5") (pinfunction "USB0_DP_5") (pintype "passive"))
    )
  )
)
